# ESP_Programming_Top.net
KiCad netlist of a schematic drawn in Altium Designer
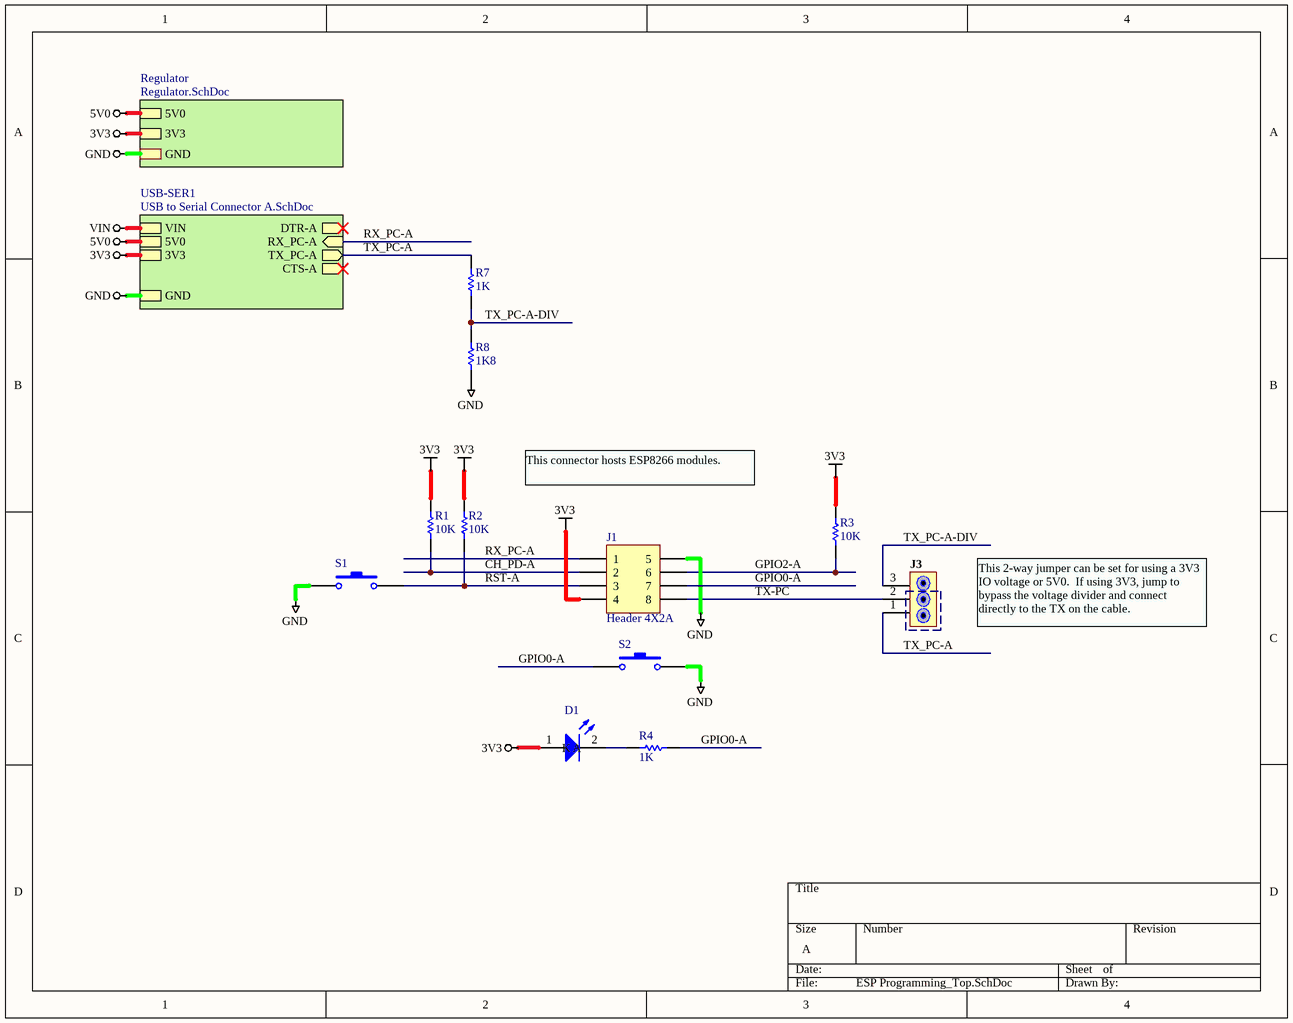
[diagram p0: ESP Programming_Top.SchDoc]

(export (version "E")
  (design (tool "Eeschema 10.0.6"))
  (components
    (comp (ref "D1")
      (value "LED2")
      (footprint "HDR1X2")
      (description "Typical RED, GREEN, YELLOW, AMBER GaAs LED")
      (fields (field (name "PUBLISHER") "Altium Limited"))
      (libsource (lib "Miscellaneous Devices") (part "LED2"))
    )
    (comp (ref "J1")
      (value "Header 4X2A")
      (footprint "HDR2X4_CEN")
      (description "Header, 4-Pin, Dual row")
      (fields (field (name "PUBLISHER") "Altium Limited"))
      (libsource (lib "Miscellaneous Connectors") (part "Header 4X2A"))
    )
    (comp (ref "J3")
      (value "3-WAY JUMPER")
      (footprint "HDR1X3")
      (description "3-Way Jumper - Center Output")
      (libsource (lib "ESP Programming") (part "3-WAY JUMPER"))
    )
    (comp (ref "R1")
      (value "10K")
      (footprint "AXIAL-0.3")
      (description "Resistor")
      (fields (field (name "Comment") "Res1") (field (name "PUBLISHER") "Altium Limited"))
      (libsource (lib "Miscellaneous Devices") (part "Res1"))
    )
    (comp (ref "R2")
      (value "10K")
      (footprint "AXIAL-0.3")
      (description "Resistor")
      (fields (field (name "Comment") "Res1") (field (name "PUBLISHER") "Altium Limited"))
      (libsource (lib "Miscellaneous Devices") (part "Res1"))
    )
    (comp (ref "R3")
      (value "10K")
      (footprint "AXIAL-0.3")
      (description "Resistor")
      (fields (field (name "Comment") "Res1") (field (name "PUBLISHER") "Altium Limited"))
      (libsource (lib "Miscellaneous Devices") (part "Res1"))
    )
    (comp (ref "R4")
      (value "1K")
      (footprint "AXIAL-0.3")
      (description "Resistor")
      (fields (field (name "Comment") "Res1") (field (name "PUBLISHER") "Altium Limited"))
      (libsource (lib "Miscellaneous Devices") (part "Res1"))
    )
    (comp (ref "R7")
      (value "1K")
      (footprint "AXIAL-0.3")
      (description "Resistor")
      (fields (field (name "Comment") "Res1") (field (name "PUBLISHER") "Altium Limited"))
      (libsource (lib "Miscellaneous Devices") (part "Res1"))
    )
    (comp (ref "R8")
      (value "1K8")
      (footprint "AXIAL-0.3")
      (description "Resistor")
      (fields (field (name "Comment") "Res1") (field (name "PUBLISHER") "Altium Limited"))
      (libsource (lib "Miscellaneous Devices") (part "Res1"))
    )
    (comp (ref "S1")
      (value "SW-PB")
      (footprint "NOPB-4")
      (description "Switch")
      (fields (field (name "PUBLISHER") "Altium Limited"))
      (libsource (lib "Miscellaneous Devices") (part "SW-PB"))
    )
    (comp (ref "S2")
      (value "SW-PB")
      (footprint "NOPB-4")
      (description "Switch")
      (fields (field (name "PUBLISHER") "Altium Limited"))
      (libsource (lib "Miscellaneous Devices") (part "SW-PB"))
    )
  )
  (nets
    (net (code "1") (name "/CH_PD-A") (class "Default")
      (node (ref "J1") (pin "2") (pinfunction "2_2") (pintype "passive"))
      (node (ref "R1") (pin "1") (pinfunction "1_1") (pintype "passive"))
    )
    (net (code "4") (name "/GPIO0-A") (class "Default")
      (node (ref "J1") (pin "7") (pinfunction "7_7") (pintype "passive"))
      (node (ref "R4") (pin "1") (pinfunction "1_1") (pintype "passive"))
      (node (ref "S2") (pin "1") (pinfunction "1_1") (pintype "passive"))
    )
    (net (code "5") (name "/GPIO2-A") (class "Default")
      (node (ref "J1") (pin "6") (pinfunction "6_6") (pintype "passive"))
      (node (ref "R3") (pin "1") (pinfunction "1_1") (pintype "passive"))
    )
    (net (code "6") (name "/RST-A") (class "Default")
      (node (ref "J1") (pin "3") (pinfunction "3_3") (pintype "passive"))
      (node (ref "R2") (pin "1") (pinfunction "1_1") (pintype "passive"))
      (node (ref "S1") (pin "2") (pinfunction "2_2") (pintype "passive"))
    )
    (net (code "7") (name "/RX_PC-A") (class "Default")
      (node (ref "J1") (pin "1") (pinfunction "1_1") (pintype "passive"))
    )
    (net (code "8") (name "/TX-PC") (class "Default")
      (node (ref "J1") (pin "8") (pinfunction "8_8") (pintype "passive"))
      (node (ref "J3") (pin "2") (pinfunction "2_2") (pintype "passive"))
    )
    (net (code "9") (name "/TX_PC-A") (class "Default")
      (node (ref "J3") (pin "1") (pinfunction "1_1") (pintype "passive"))
      (node (ref "R7") (pin "2") (pinfunction "2_2") (pintype "passive"))
    )
    (net (code "10") (name "/TX_PC-A-DIV") (class "Default")
      (node (ref "J3") (pin "3") (pinfunction "3_3") (pintype "passive"))
      (node (ref "R7") (pin "1") (pinfunction "1_1") (pintype "passive"))
      (node (ref "R8") (pin "2") (pinfunction "2_2") (pintype "passive"))
    )
    (net (code "11") (name "3V3") (class "Default")
      (node (ref "D1") (pin "1") (pinfunction "A_1") (pintype "passive"))
      (node (ref "J1") (pin "4") (pinfunction "4_4") (pintype "passive"))
      (node (ref "R1") (pin "2") (pinfunction "2_2") (pintype "passive"))
      (node (ref "R2") (pin "2") (pinfunction "2_2") (pintype "passive"))
      (node (ref "R3") (pin "2") (pinfunction "2_2") (pintype "passive"))
    )
    (net (code "13") (name "GND") (class "Default")
      (node (ref "J1") (pin "5") (pinfunction "5_5") (pintype "passive"))
      (node (ref "R8") (pin "1") (pinfunction "1_1") (pintype "passive"))
      (node (ref "S1") (pin "1") (pinfunction "1_1") (pintype "passive"))
      (node (ref "S2") (pin "2") (pinfunction "2_2") (pintype "passive"))
    )
    (net (code "14") (name "Net-(D1-K)") (class "Default")
      (node (ref "D1") (pin "2") (pinfunction "K_2") (pintype "passive"))
      (node (ref "R4") (pin "2") (pinfunction "2_2") (pintype "passive"))
    )
  )
)
